# Eagle_Dio_Faziko_Pratama.net
KiCad netlist of a schematic drawn in EAGLE
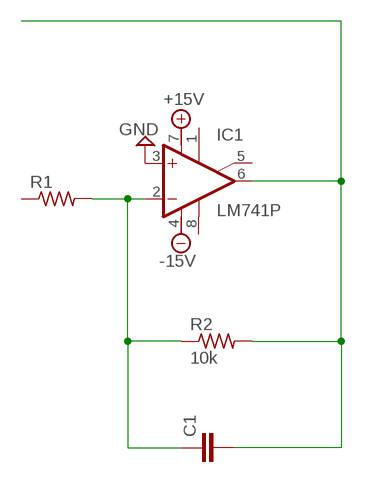
[diagram p0: schematic, sheet 1]

(export (version "E")
  (design (tool "Eeschema 10.0.6"))
  (components
    (comp (ref "C1")
      (value "2uF")
      (footprint "eagle-import:C2.5-3")
      (libsource (lib "eagle-import") (part "C2,5-3"))
    )
    (comp (ref "IC1")
      (value "LM741P")
      (footprint "eagle-import:DIL08")
      (libsource (lib "eagle-import") (part "741PLM"))
    )
    (comp (ref "R1")
      (value "R-US_0204/2V")
      (footprint "eagle-import:0204V")
      (libsource (lib "eagle-import") (part "R-US_0204/2V"))
    )
    (comp (ref "R2")
      (value "10k")
      (footprint "eagle-import:0204V")
      (libsource (lib "eagle-import") (part "R-US_0204/2V"))
    )
  )
  (nets
    (net (code "3") (name "/V+") (class "Default")
      (node (ref "IC1") (pin "7") (pinfunction "V+_7") (pintype "power_in"))
    )
    (net (code "4") (name "/V-") (class "Default")
      (node (ref "IC1") (pin "4") (pinfunction "V-_4") (pintype "power_in"))
    )
    (net (code "5") (name "GND") (class "Default")
      (node (ref "IC1") (pin "3") (pinfunction "+IN_3") (pintype "input"))
    )
    (net (code "6") (name "Net-(IC1--IN)") (class "Default")
      (node (ref "C1") (pin "1") (pinfunction "1_1") (pintype "passive"))
      (node (ref "IC1") (pin "2") (pinfunction "-IN_2") (pintype "input"))
      (node (ref "R1") (pin "2") (pinfunction "2_2") (pintype "passive"))
      (node (ref "R2") (pin "1") (pinfunction "1_1") (pintype "passive"))
    )
    (net (code "7") (name "Net-(IC1-OUT)") (class "Default")
      (node (ref "C1") (pin "2") (pinfunction "2_2") (pintype "passive"))
      (node (ref "IC1") (pin "6") (pinfunction "OUT_6") (pintype "output"))
      (node (ref "R2") (pin "2") (pinfunction "2_2") (pintype "passive"))
    )
    (net (code "8") (name "unconnected-(IC1-ON1-Pad1)") (class "Default")
      (node (ref "IC1") (pin "1") (pinfunction "ON1_1") (pintype "passive"))
    )
    (net (code "9") (name "unconnected-(IC1-ON2-Pad5)") (class "Default")
      (node (ref "IC1") (pin "5") (pinfunction "ON2_5") (pintype "passive"))
    )
    (net (code "10") (name "unconnected-(IC1-OPT-Pad8)") (class "Default")
      (node (ref "IC1") (pin "8") (pinfunction "OPT_8") (pintype "passive"))
    )
    (net (code "11") (name "unconnected-(R1-Pad1)") (class "Default")
      (node (ref "R1") (pin "1") (pinfunction "1_1") (pintype "passive"))
    )
  )
)
